# DHT11.net
KiCad netlist of a schematic drawn in Altium Designer
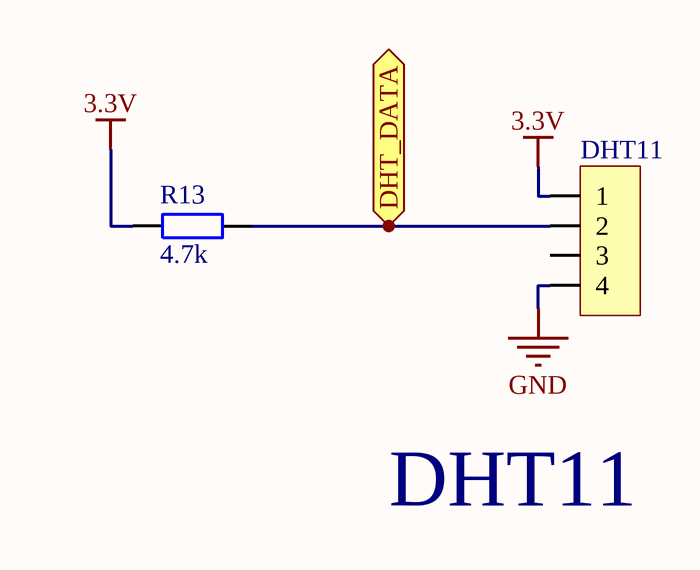
[diagram p0: DHT11.SchDoc]

(export (version "E")
  (design (tool "Eeschema 10.0.6"))
  (components
    (comp (ref "DHT11")
      (value "JP 1x4 2.54")
      (footprint "JP 1x4 CT")
      (description "Cắm")
      (libsource (lib "Altium_Lib_by_KhueNguyenCreator") (part "JP 1x4 2.54 Cai Thang"))
    )
    (comp (ref "R13")
      (value "4.7k")
      (footprint "tro smd 0603")
      (description "Dán")
      (libsource (lib "Altium_Lib_by_KhueNguyenCreator") (part "Tro 0603 5% 4.7k"))
    )
  )
  (nets
    (net (code "1") (name "/DHT_DATA") (class "Default")
      (node (ref "DHT11") (pin "2") (pinfunction "2_2") (pintype "passive"))
      (node (ref "R13") (pin "2") (pinfunction "2_2") (pintype "passive"))
    )
    (net (code "2") (name "3.3V") (class "Default")
      (node (ref "DHT11") (pin "1") (pinfunction "1_1") (pintype "passive"))
      (node (ref "R13") (pin "1") (pinfunction "1_1") (pintype "passive"))
    )
    (net (code "3") (name "GND") (class "Default")
      (node (ref "DHT11") (pin "4") (pinfunction "4_4") (pintype "passive"))
    )
    (net (code "4") (name "unconnected-(DHT11-Pad3)") (class "Default")
      (node (ref "DHT11") (pin "3") (pinfunction "3_3") (pintype "passive"))
    )
  )
)
